# DenHoc_Arduino.net
KiCad netlist of a schematic drawn in Altium Designer
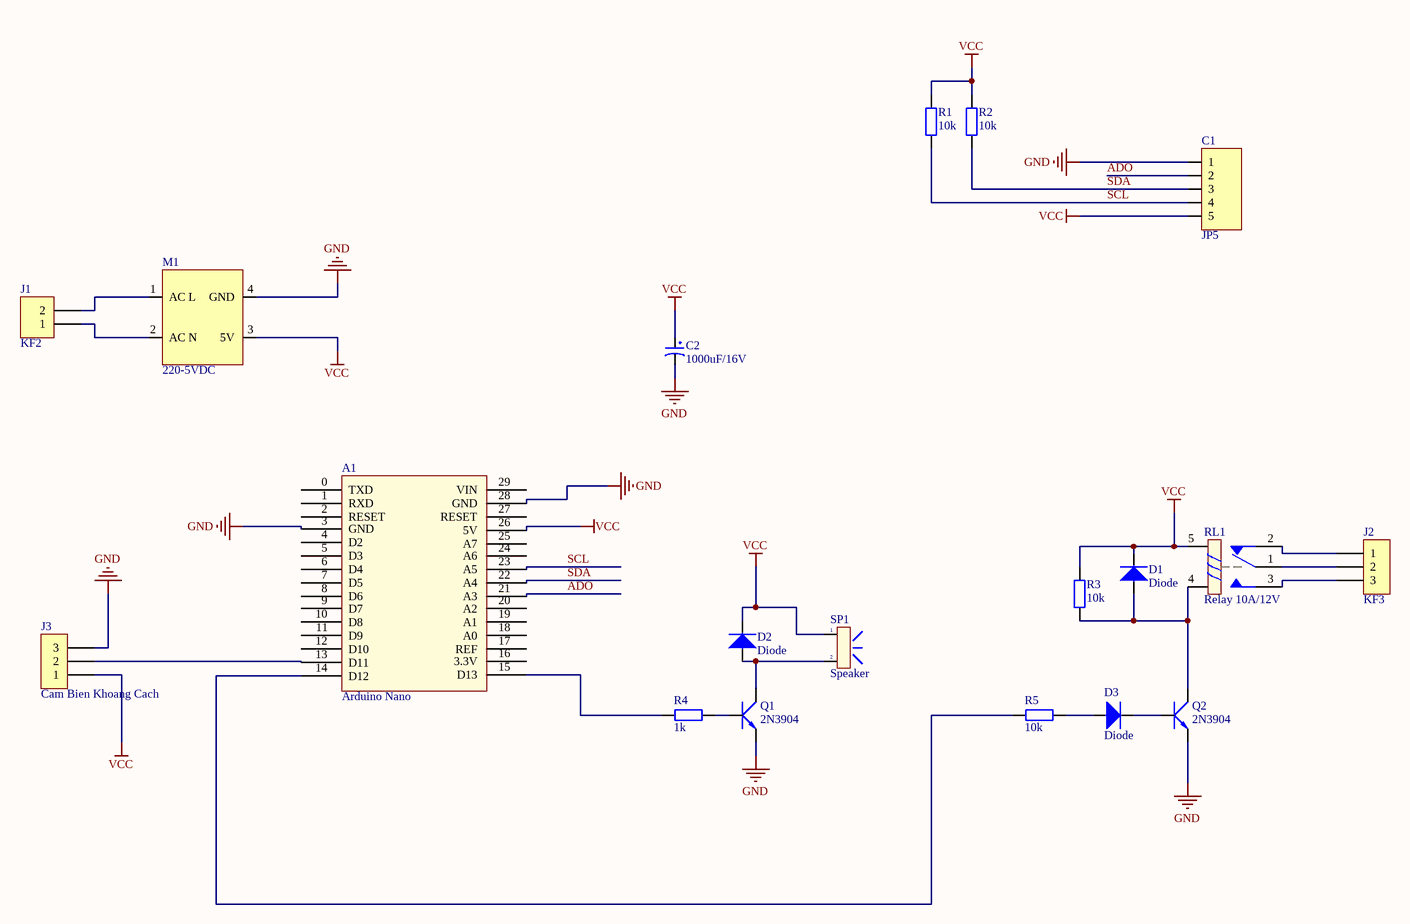
[diagram p0: DenHoc_Arduino.SchDoc]

(export (version "E")
  (design (tool "Eeschema 10.0.6"))
  (components
    (comp (ref "A1")
      (value "Arduino Nano")
      (footprint "Arduino Nano_JUMP")
      (libsource (lib "OBIT_TESLA") (part "Arduino Nano"))
    )
    (comp (ref "C1")
      (value "JP5")
      (footprint "JP5-C1T")
      (description "WR-PHD 2.54 mm Angled Socket Header")
      (fields
        (field (name "MANUFACTURER") "Würth Elektronik eiSos GmbH")
        (field (name "PARTNO") "613005143121")
        (field (name "CREATED BY") "Karrer Zheng")
      )
      (libsource (lib "OBIT_TESLA") (part "JP5"))
    )
    (comp (ref "C2")
      (value "1000uF/16V")
      (footprint "CP1.5/3.4")
      (description "Cap 1000uF/16V - 220uF/50V")
      (libsource (lib "OBIT_TESLA") (part "CP4"))
    )
    (comp (ref "D1") (value "Diode") (footprint "DIO-SMD-106") (libsource (lib "OBIT_TESLA") (part "Diode")))
    (comp (ref "D2") (value "Diode") (footprint "DIO-SMD-106") (libsource (lib "OBIT_TESLA") (part "Diode")))
    (comp (ref "D3") (value "Diode") (footprint "DIO-SMD-106") (libsource (lib "OBIT_TESLA") (part "Diode")))
    (comp (ref "J1")
      (value "KF2")
      (footprint "KF2-3.5")
      (fields
        (field (name "MANUFACTURER") "Würth Elektronik eiSos GmbH")
        (field (name "PARTNO") "691103110002")
        (field (name "CREATED BY") "Karrer Zheng")
      )
      (libsource (lib "OBIT_TESLA") (part "KF2"))
    )
    (comp (ref "J2")
      (value "KF3")
      (footprint "KF3-5.08")
      (fields
        (field (name "MANUFACTURER") "Würth Elektronik eiSos GmbH")
        (field (name "PARTNO") "691103110003")
        (field (name "CREATED BY") "Karrer Zheng")
      )
      (libsource (lib "OBIT_TESLA") (part "KF3"))
    )
    (comp (ref "J3")
      (value "Cam Bien Khoang Cach")
      (footprint "KF3-5.08")
      (fields
        (field (name "MANUFACTURER") "Würth Elektronik eiSos GmbH")
        (field (name "PARTNO") "691103110003")
        (field (name "CREATED BY") "Karrer Zheng")
      )
      (libsource (lib "") (part "KF3_1"))
    )
    (comp (ref "M1")
      (value "220-5VDC")
      (footprint "5V 700mA 3.5W AC DC")
      (libsource (lib "OBIT_TESLA") (part "5V 700mA 3.5W AC 220 to DC"))
    )
    (comp (ref "Q1")
      (value "2N3904")
      (footprint "TO92-123")
      (description "NPN 600mW, ECB")
      (libsource (lib "OBIT_TESLA") (part "2N3904"))
    )
    (comp (ref "Q2")
      (value "2N3904")
      (footprint "TO92-123")
      (description "NPN 600mW, ECB")
      (libsource (lib "OBIT_TESLA") (part "2N3904"))
    )
    (comp (ref "R1")
      (value "10k")
      (footprint "RES-1/4W")
      (description "Resistor R1/4W")
      (libsource (lib "OBIT_TESLA") (part "R"))
    )
    (comp (ref "R2")
      (value "10k")
      (footprint "RES-1/4W")
      (description "Resistor R1/4W")
      (libsource (lib "OBIT_TESLA") (part "R"))
    )
    (comp (ref "R3")
      (value "10k")
      (footprint "RES-1/4W")
      (description "Resistor R1/4W")
      (libsource (lib "OBIT_TESLA") (part "R"))
    )
    (comp (ref "R4")
      (value "1k")
      (footprint "RES-1/4W")
      (description "Resistor R1/4W")
      (libsource (lib "OBIT_TESLA") (part "R"))
    )
    (comp (ref "R5")
      (value "10k")
      (footprint "RES-1/4W")
      (description "Resistor R1/4W")
      (libsource (lib "OBIT_TESLA") (part "R"))
    )
    (comp (ref "RL1")
      (value "Relay 10A/12V")
      (footprint "RL_SPDT_10A")
      (description "Relay SPDT,10A - 12VDC 5 Pin")
      (libsource (lib "OBIT_TESLA") (part "Relay 1"))
    )
    (comp (ref "SP1")
      (value "Speaker")
      (footprint "SPK")
      (description "Speaker Chip")
      (libsource (lib "OBIT_TESLA") (part "SPK"))
    )
  )
  (nets
    (net (code "1") (name "/ADO") (class "Default")
      (node (ref "A1") (pin "21") (pinfunction "A3_21") (pintype "passive"))
      (node (ref "C1") (pin "2") (pinfunction "2_2") (pintype "passive"))
    )
    (net (code "2") (name "/SCL") (class "Default")
      (node (ref "A1") (pin "23") (pinfunction "A5_23") (pintype "passive"))
      (node (ref "C1") (pin "4") (pinfunction "4_4") (pintype "passive"))
      (node (ref "R1") (pin "1") (pinfunction "1_1") (pintype "passive"))
    )
    (net (code "3") (name "/SDA") (class "Default")
      (node (ref "A1") (pin "22") (pinfunction "A4_22") (pintype "passive"))
      (node (ref "C1") (pin "3") (pinfunction "3_3") (pintype "passive"))
      (node (ref "R2") (pin "1") (pinfunction "1_1") (pintype "passive"))
    )
    (net (code "4") (name "GND") (class "Default")
      (node (ref "A1") (pin "28") (pinfunction "GND_28") (pintype "passive"))
      (node (ref "A1") (pin "3") (pinfunction "GND_3") (pintype "passive"))
      (node (ref "C1") (pin "1") (pinfunction "1_1") (pintype "passive"))
      (node (ref "C2") (pin "2") (pinfunction "2_2") (pintype "passive"))
      (node (ref "J3") (pin "3") (pinfunction "3_3") (pintype "passive"))
      (node (ref "M1") (pin "4") (pinfunction "GND_4") (pintype "passive"))
      (node (ref "Q1") (pin "1") (pinfunction "E_1") (pintype "passive"))
      (node (ref "Q2") (pin "1") (pinfunction "E_1") (pintype "passive"))
    )
    (net (code "5") (name "Net-(A1-D11)") (class "Default")
      (node (ref "A1") (pin "13") (pinfunction "D11_13") (pintype "passive"))
      (node (ref "J3") (pin "2") (pinfunction "2_2") (pintype "passive"))
    )
    (net (code "6") (name "Net-(A1-D12)") (class "Default")
      (node (ref "A1") (pin "14") (pinfunction "D12_14") (pintype "passive"))
      (node (ref "R5") (pin "2") (pinfunction "2_2") (pintype "passive"))
    )
    (net (code "7") (name "Net-(A1-D13)") (class "Default")
      (node (ref "A1") (pin "15") (pinfunction "D13_15") (pintype "passive"))
      (node (ref "R4") (pin "2") (pinfunction "2_2") (pintype "passive"))
    )
    (net (code "8") (name "Net-(D3-Pad1)") (class "Default")
      (node (ref "D3") (pin "1") (pinfunction "1_1") (pintype "passive"))
      (node (ref "R5") (pin "1") (pinfunction "1_1") (pintype "passive"))
    )
    (net (code "9") (name "Net-(J2-Pad1)") (class "Default")
      (node (ref "J2") (pin "1") (pinfunction "1_1") (pintype "passive"))
      (node (ref "RL1") (pin "2") (pinfunction "2_2") (pintype "passive"))
    )
    (net (code "10") (name "Net-(J2-Pad2)") (class "Default")
      (node (ref "J2") (pin "2") (pinfunction "2_2") (pintype "passive"))
      (node (ref "RL1") (pin "1") (pinfunction "1_1") (pintype "passive"))
    )
    (net (code "11") (name "Net-(J2-Pad3)") (class "Default")
      (node (ref "J2") (pin "3") (pinfunction "3_3") (pintype "passive"))
      (node (ref "RL1") (pin "3") (pinfunction "3_3") (pintype "passive"))
    )
    (net (code "12") (name "Net-(M1-AC_L)") (class "Default")
      (node (ref "J1") (pin "2") (pinfunction "2_2") (pintype "passive"))
      (node (ref "M1") (pin "1") (pinfunction "AC_L_1") (pintype "passive"))
    )
    (net (code "13") (name "Net-(M1-AC_N)") (class "Default")
      (node (ref "J1") (pin "1") (pinfunction "1_1") (pintype "passive"))
      (node (ref "M1") (pin "2") (pinfunction "AC_N_2") (pintype "passive"))
    )
    (net (code "14") (name "Net-(Q1-B)") (class "Default")
      (node (ref "Q1") (pin "2") (pinfunction "B_2") (pintype "passive"))
      (node (ref "R4") (pin "1") (pinfunction "1_1") (pintype "passive"))
    )
    (net (code "15") (name "Net-(Q1-C)") (class "Default")
      (node (ref "D2") (pin "1") (pinfunction "1_1") (pintype "passive"))
      (node (ref "Q1") (pin "3") (pinfunction "C_3") (pintype "passive"))
      (node (ref "SP1") (pin "2") (pinfunction "2_2") (pintype "passive"))
    )
    (net (code "16") (name "Net-(Q2-B)") (class "Default")
      (node (ref "D3") (pin "2") (pinfunction "2_2") (pintype "passive"))
      (node (ref "Q2") (pin "2") (pinfunction "B_2") (pintype "passive"))
    )
    (net (code "17") (name "Net-(Q2-C)") (class "Default")
      (node (ref "D1") (pin "1") (pinfunction "1_1") (pintype "passive"))
      (node (ref "Q2") (pin "3") (pinfunction "C_3") (pintype "passive"))
      (node (ref "R3") (pin "1") (pinfunction "1_1") (pintype "passive"))
      (node (ref "RL1") (pin "4") (pinfunction "4_4") (pintype "passive"))
    )
    (net (code "18") (name "VCC") (class "Default")
      (node (ref "A1") (pin "26") (pinfunction "5V_26") (pintype "passive"))
      (node (ref "C1") (pin "5") (pinfunction "5_5") (pintype "passive"))
      (node (ref "C2") (pin "1") (pinfunction "1_1") (pintype "passive"))
      (node (ref "D1") (pin "2") (pinfunction "2_2") (pintype "passive"))
      (node (ref "D2") (pin "2") (pinfunction "2_2") (pintype "passive"))
      (node (ref "J3") (pin "1") (pinfunction "1_1") (pintype "passive"))
      (node (ref "M1") (pin "3") (pinfunction "5V_3") (pintype "passive"))
      (node (ref "R1") (pin "2") (pinfunction "2_2") (pintype "passive"))
      (node (ref "R2") (pin "2") (pinfunction "2_2") (pintype "passive"))
      (node (ref "R3") (pin "2") (pinfunction "2_2") (pintype "passive"))
      (node (ref "RL1") (pin "5") (pinfunction "5_5") (pintype "passive"))
      (node (ref "SP1") (pin "1") (pinfunction "1_1") (pintype "passive"))
    )
    (net (code "19") (name "unconnected-(A1-3.3V-Pad16)") (class "Default")
      (node (ref "A1") (pin "16") (pinfunction "3.3V_16") (pintype "passive"))
    )
    (net (code "20") (name "unconnected-(A1-A0-Pad18)") (class "Default")
      (node (ref "A1") (pin "18") (pinfunction "A0_18") (pintype "passive"))
    )
    (net (code "21") (name "unconnected-(A1-A1-Pad19)") (class "Default")
      (node (ref "A1") (pin "19") (pinfunction "A1_19") (pintype "passive"))
    )
    (net (code "22") (name "unconnected-(A1-A2-Pad20)") (class "Default")
      (node (ref "A1") (pin "20") (pinfunction "A2_20") (pintype "passive"))
    )
    (net (code "23") (name "unconnected-(A1-A6-Pad24)") (class "Default")
      (node (ref "A1") (pin "24") (pinfunction "A6_24") (pintype "passive"))
    )
    (net (code "24") (name "unconnected-(A1-A7-Pad25)") (class "Default")
      (node (ref "A1") (pin "25") (pinfunction "A7_25") (pintype "passive"))
    )
    (net (code "25") (name "unconnected-(A1-D2-Pad4)") (class "Default")
      (node (ref "A1") (pin "4") (pinfunction "D2_4") (pintype "passive"))
    )
    (net (code "26") (name "unconnected-(A1-D3-Pad5)") (class "Default")
      (node (ref "A1") (pin "5") (pinfunction "D3_5") (pintype "passive"))
    )
    (net (code "27") (name "unconnected-(A1-D4-Pad6)") (class "Default")
      (node (ref "A1") (pin "6") (pinfunction "D4_6") (pintype "passive"))
    )
    (net (code "28") (name "unconnected-(A1-D5-Pad7)") (class "Default")
      (node (ref "A1") (pin "7") (pinfunction "D5_7") (pintype "passive"))
    )
    (net (code "29") (name "unconnected-(A1-D6-Pad8)") (class "Default")
      (node (ref "A1") (pin "8") (pinfunction "D6_8") (pintype "passive"))
    )
    (net (code "30") (name "unconnected-(A1-D7-Pad9)") (class "Default")
      (node (ref "A1") (pin "9") (pinfunction "D7_9") (pintype "passive"))
    )
    (net (code "31") (name "unconnected-(A1-D8-Pad10)") (class "Default")
      (node (ref "A1") (pin "10") (pinfunction "D8_10") (pintype "passive"))
    )
    (net (code "32") (name "unconnected-(A1-D9-Pad11)") (class "Default")
      (node (ref "A1") (pin "11") (pinfunction "D9_11") (pintype "passive"))
    )
    (net (code "33") (name "unconnected-(A1-D10-Pad12)") (class "Default")
      (node (ref "A1") (pin "12") (pinfunction "D10_12") (pintype "passive"))
    )
    (net (code "34") (name "unconnected-(A1-REF-Pad17)") (class "Default")
      (node (ref "A1") (pin "17") (pinfunction "REF_17") (pintype "passive"))
    )
    (net (code "35") (name "unconnected-(A1-RESET-Pad2)") (class "Default")
      (node (ref "A1") (pin "2") (pinfunction "RESET_2") (pintype "passive"))
    )
    (net (code "36") (name "unconnected-(A1-RESET-Pad27)") (class "Default")
      (node (ref "A1") (pin "27") (pinfunction "RESET_27") (pintype "passive"))
    )
    (net (code "37") (name "unconnected-(A1-RXD-Pad1)") (class "Default")
      (node (ref "A1") (pin "1") (pinfunction "RXD_1") (pintype "passive"))
    )
    (net (code "38") (name "unconnected-(A1-TXD-Pad0)") (class "Default")
      (node (ref "A1") (pin "0") (pinfunction "TXD_0") (pintype "passive"))
    )
    (net (code "39") (name "unconnected-(A1-VIN-Pad29)") (class "Default")
      (node (ref "A1") (pin "29") (pinfunction "VIN_29") (pintype "passive"))
    )
  )
)
